# USB.net
KiCad netlist of a schematic drawn in Altium Designer
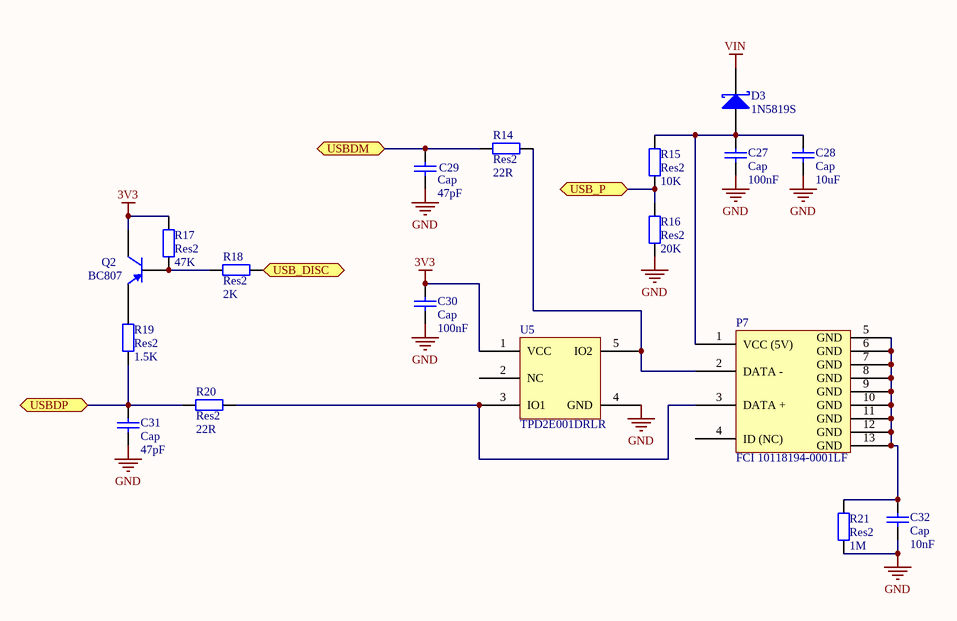
[diagram p0: USB.SchDoc]

(export (version "E")
  (design (tool "Eeschema 10.0.6"))
  (components
    (comp (ref "C27")
      (value "Cap")
      (footprint "0603")
      (description "Capacitor")
      (fields (field (name "ALTIUM_VALUE") "100nF"))
      (libsource (lib "Miscellaneous Devices") (part "Cap"))
    )
    (comp (ref "C28")
      (value "Cap")
      (footprint "0805")
      (description "Capacitor")
      (fields (field (name "ALTIUM_VALUE") "10uF"))
      (libsource (lib "Miscellaneous Devices") (part "Cap"))
    )
    (comp (ref "C29")
      (value "Cap")
      (footprint "0603")
      (description "Capacitor")
      (fields
        (field (name "ALTIUM_VALUE") "47pF")
        (field (name "MANUFACTURER") "Samsung Electro-Mechanics America, Inc")
        (field (name "MANUFACTURER PART NUMBER") "CL10C470JB8NCNC")
      )
      (libsource (lib "Miscellaneous Devices") (part "Cap"))
    )
    (comp (ref "C30")
      (value "Cap")
      (footprint "0603")
      (description "Capacitor")
      (fields (field (name "ALTIUM_VALUE") "100nF"))
      (libsource (lib "Miscellaneous Devices") (part "Cap"))
    )
    (comp (ref "C31")
      (value "Cap")
      (footprint "0603")
      (description "Capacitor")
      (fields
        (field (name "ALTIUM_VALUE") "47pF")
        (field (name "MANUFACTURER") "Samsung Electro-Mechanics America, Inc")
        (field (name "MANUFACTURER PART NUMBER") "CL10C470JB8NCNC")
      )
      (libsource (lib "Miscellaneous Devices") (part "Cap"))
    )
    (comp (ref "C32")
      (value "Cap")
      (footprint "0603")
      (description "Capacitor")
      (fields
        (field (name "ALTIUM_VALUE") "10nF")
        (field (name "MANUFACTURER") "Samsung Electro-Mechanics America, Inc")
        (field (name "MANUFACTURER PART NUMBER") "CL10B103JB8NNNC")
      )
      (libsource (lib "Miscellaneous Devices") (part "Cap"))
    )
    (comp (ref "D3")
      (value "1N5819S")
      (footprint "SMB")
      (description "Schottky Diode")
      (fields
        (field (name "MANUFACTURER") "Diodes Incorporated")
        (field (name "MANUFACTURER PART NUMBER") "1N5819HW-7-F")
        (field (name "PUBLISHER") "Altium Limited")
      )
      (libsource (lib "Miscellaneous Devices") (part "D Schottky"))
    )
    (comp (ref "P7")
      (value "FCI 10118194-0001LF")
      (footprint "CONN USB MICRO B RECPT SMT R/A")
      (description "CONN USB MICRO B RECPT SMT R/A")
      (libsource (lib "BrewBit") (part "FCI 10118194-0001LF"))
    )
    (comp (ref "Q2")
      (value "BC807")
      (footprint "SOT-23B_L")
      (description "PNP Bipolar Transistor")
      (fields
        (field (name "MANUFACTURER") "NXP Semiconductors")
        (field (name "MANUFACTURER PART NUMBER") "BC807-40,215")
        (field (name "PUBLISHER") "Altium Limited")
      )
      (libsource (lib "Miscellaneous Devices") (part "PNP"))
    )
    (comp (ref "R14")
      (value "Res2")
      (footprint "0603")
      (description "Resistor")
      (fields
        (field (name "ALTIUM_VALUE") "22R")
        (field (name "MANUFACTURER") "Panasonic Electronic Components")
        (field (name "MANUFACTURER PART NUMBER") "ERJ-3EKF22R0V")
      )
      (libsource (lib "") (part "Res2_1"))
    )
    (comp (ref "R15")
      (value "Res2")
      (footprint "0603")
      (description "Resistor")
      (fields
        (field (name "ALTIUM_VALUE") "10K")
        (field (name "MANUFACTURER") "Panasonic Electronic Components")
        (field (name "MANUFACTURER PART NUMBER") "ERJ-3GEYJ103V")
      )
      (libsource (lib "") (part "Res2_2"))
    )
    (comp (ref "R16")
      (value "Res2")
      (footprint "0603")
      (description "Resistor")
      (fields
        (field (name "ALTIUM_VALUE") "20K")
        (field (name "MANUFACTURER") "Samsung Electro-Mechanics America, Inc")
        (field (name "MANUFACTURER PART NUMBER") "RC1608F203CS")
      )
      (libsource (lib "") (part "Res2_2"))
    )
    (comp (ref "R17")
      (value "Res2")
      (footprint "0603")
      (description "Resistor")
      (fields
        (field (name "ALTIUM_VALUE") "47K")
        (field (name "MANUFACTURER") "Samsung Electro-Mechanics America, Inc")
        (field (name "MANUFACTURER PART NUMBER") "RC1608F473CS")
      )
      (libsource (lib "Miscellaneous Devices") (part "Res2"))
    )
    (comp (ref "R18")
      (value "Res2")
      (footprint "0603")
      (description "Resistor")
      (fields
        (field (name "ALTIUM_VALUE") "2K")
        (field (name "MANUFACTURER") "Samsung Electro-Mechanics America, Inc")
        (field (name "MANUFACTURER PART NUMBER") "RC1608F202CS")
      )
      (libsource (lib "") (part "Res2_3"))
    )
    (comp (ref "R19")
      (value "Res2")
      (footprint "0603")
      (description "Resistor")
      (fields
        (field (name "ALTIUM_VALUE") "1.5K")
        (field (name "MANUFACTURER") "Samsung Electro-Mechanics America, Inc")
        (field (name "MANUFACTURER PART NUMBER") "RC1608F152CS")
      )
      (libsource (lib "Miscellaneous Devices") (part "Res2"))
    )
    (comp (ref "R20")
      (value "Res2")
      (footprint "0603")
      (description "Resistor")
      (fields
        (field (name "ALTIUM_VALUE") "22R")
        (field (name "MANUFACTURER") "Panasonic Electronic Components")
        (field (name "MANUFACTURER PART NUMBER") "ERJ-3EKF22R0V")
      )
      (libsource (lib "") (part "Res2_1"))
    )
    (comp (ref "R21")
      (value "Res2")
      (footprint "0603")
      (description "Resistor")
      (fields
        (field (name "ALTIUM_VALUE") "1M")
        (field (name "MANUFACTURER") "Yageo")
        (field (name "MANUFACTURER PART NUMBER") "RC0603FR-071ML")
      )
      (libsource (lib "Miscellaneous Devices") (part "Res2"))
    )
    (comp (ref "U5")
      (value "TPD2E001DRLR")
      (footprint "SOT-553")
      (description "TVS DIODE 5.5VWM 100VC SOT5")
      (fields (field (name "MANUFACTURER") "Texas Instruments"))
      (libsource (lib "BrewBit") (part "TPD2E001DRLR"))
    )
  )
  (nets
    (net (code "1") (name "/USBDM") (class "Default")
      (node (ref "C29") (pin "2") (pinfunction "2_2") (pintype "passive"))
      (node (ref "R14") (pin "2") (pinfunction "2_2") (pintype "passive"))
    )
    (net (code "2") (name "/USBDP") (class "Default")
      (node (ref "C31") (pin "2") (pinfunction "2_2") (pintype "passive"))
      (node (ref "R19") (pin "2") (pinfunction "2_2") (pintype "passive"))
      (node (ref "R20") (pin "2") (pinfunction "2_2") (pintype "passive"))
    )
    (net (code "3") (name "/USB_DISC") (class "Default")
      (node (ref "R18") (pin "2") (pinfunction "2_2") (pintype "passive"))
    )
    (net (code "4") (name "/USB_P") (class "Default")
      (node (ref "R15") (pin "1") (pinfunction "1_1") (pintype "passive"))
      (node (ref "R16") (pin "2") (pinfunction "2_2") (pintype "passive"))
    )
    (net (code "5") (name "3V3") (class "Default")
      (node (ref "C30") (pin "2") (pinfunction "2_2") (pintype "passive"))
      (node (ref "Q2") (pin "1") (pinfunction "C_1") (pintype "passive"))
      (node (ref "R17") (pin "1") (pinfunction "1_1") (pintype "passive"))
      (node (ref "U5") (pin "1") (pinfunction "VCC_1") (pintype "passive"))
    )
    (net (code "6") (name "GND") (class "Default")
      (node (ref "C27") (pin "1") (pinfunction "1_1") (pintype "passive"))
      (node (ref "C28") (pin "1") (pinfunction "1_1") (pintype "passive"))
      (node (ref "C29") (pin "1") (pinfunction "1_1") (pintype "passive"))
      (node (ref "C30") (pin "1") (pinfunction "1_1") (pintype "passive"))
      (node (ref "C31") (pin "1") (pinfunction "1_1") (pintype "passive"))
      (node (ref "C32") (pin "1") (pinfunction "1_1") (pintype "passive"))
      (node (ref "R16") (pin "1") (pinfunction "1_1") (pintype "passive"))
      (node (ref "R21") (pin "2") (pinfunction "2_2") (pintype "passive"))
      (node (ref "U5") (pin "4") (pinfunction "GND_4") (pintype "passive"))
    )
    (net (code "7") (name "Net-(C32-Pad2)") (class "Default")
      (node (ref "C32") (pin "2") (pinfunction "2_2") (pintype "passive"))
      (node (ref "P7") (pin "10") (pinfunction "GND_10") (pintype "passive"))
      (node (ref "P7") (pin "11") (pinfunction "GND_11") (pintype "passive"))
      (node (ref "P7") (pin "12") (pinfunction "GND_12") (pintype "passive"))
      (node (ref "P7") (pin "13") (pinfunction "GND_13") (pintype "passive"))
      (node (ref "P7") (pin "5") (pinfunction "GND_5") (pintype "passive"))
      (node (ref "P7") (pin "6") (pinfunction "GND_6") (pintype "passive"))
      (node (ref "P7") (pin "7") (pinfunction "GND_7") (pintype "passive"))
      (node (ref "P7") (pin "8") (pinfunction "GND_8") (pintype "passive"))
      (node (ref "P7") (pin "9") (pinfunction "GND_9") (pintype "passive"))
      (node (ref "R21") (pin "1") (pinfunction "1_1") (pintype "passive"))
    )
    (net (code "8") (name "Net-(D3-A)") (class "Default")
      (node (ref "C27") (pin "2") (pinfunction "2_2") (pintype "passive"))
      (node (ref "C28") (pin "2") (pinfunction "2_2") (pintype "passive"))
      (node (ref "D3") (pin "1") (pinfunction "A_1") (pintype "passive"))
      (node (ref "P7") (pin "1") (pinfunction "VCC_(5V)_1") (pintype "passive"))
      (node (ref "R15") (pin "2") (pinfunction "2_2") (pintype "passive"))
    )
    (net (code "9") (name "Net-(P7-DATA_+)") (class "Default")
      (node (ref "P7") (pin "3") (pinfunction "DATA_+_3") (pintype "passive"))
      (node (ref "R20") (pin "1") (pinfunction "1_1") (pintype "passive"))
      (node (ref "U5") (pin "3") (pinfunction "IO1_3") (pintype "passive"))
    )
    (net (code "10") (name "Net-(P7-DATA_-)") (class "Default")
      (node (ref "P7") (pin "2") (pinfunction "DATA_-_2") (pintype "passive"))
      (node (ref "R14") (pin "1") (pinfunction "1_1") (pintype "passive"))
      (node (ref "U5") (pin "5") (pinfunction "IO2_5") (pintype "passive"))
    )
    (net (code "11") (name "Net-(Q2-B)") (class "Default")
      (node (ref "Q2") (pin "2") (pinfunction "B_2") (pintype "passive"))
      (node (ref "R17") (pin "2") (pinfunction "2_2") (pintype "passive"))
      (node (ref "R18") (pin "1") (pinfunction "1_1") (pintype "passive"))
    )
    (net (code "12") (name "Net-(Q2-E)") (class "Default")
      (node (ref "Q2") (pin "3") (pinfunction "E_3") (pintype "passive"))
      (node (ref "R19") (pin "1") (pinfunction "1_1") (pintype "passive"))
    )
    (net (code "13") (name "VIN") (class "Default")
      (node (ref "D3") (pin "2") (pinfunction "K_2") (pintype "passive"))
    )
    (net (code "14") (name "unconnected-(P7-ID_(NC)-Pad4)") (class "Default")
      (node (ref "P7") (pin "4") (pinfunction "ID_(NC)_4") (pintype "passive"))
    )
    (net (code "15") (name "unconnected-(U5-NC-Pad2)") (class "Default")
      (node (ref "U5") (pin "2") (pinfunction "NC_2") (pintype "passive"))
    )
  )
)
